# LB_BIT_i2_TOGGLESWITCH-v02_rev1.net
KiCad netlist of a schematic drawn in EAGLE
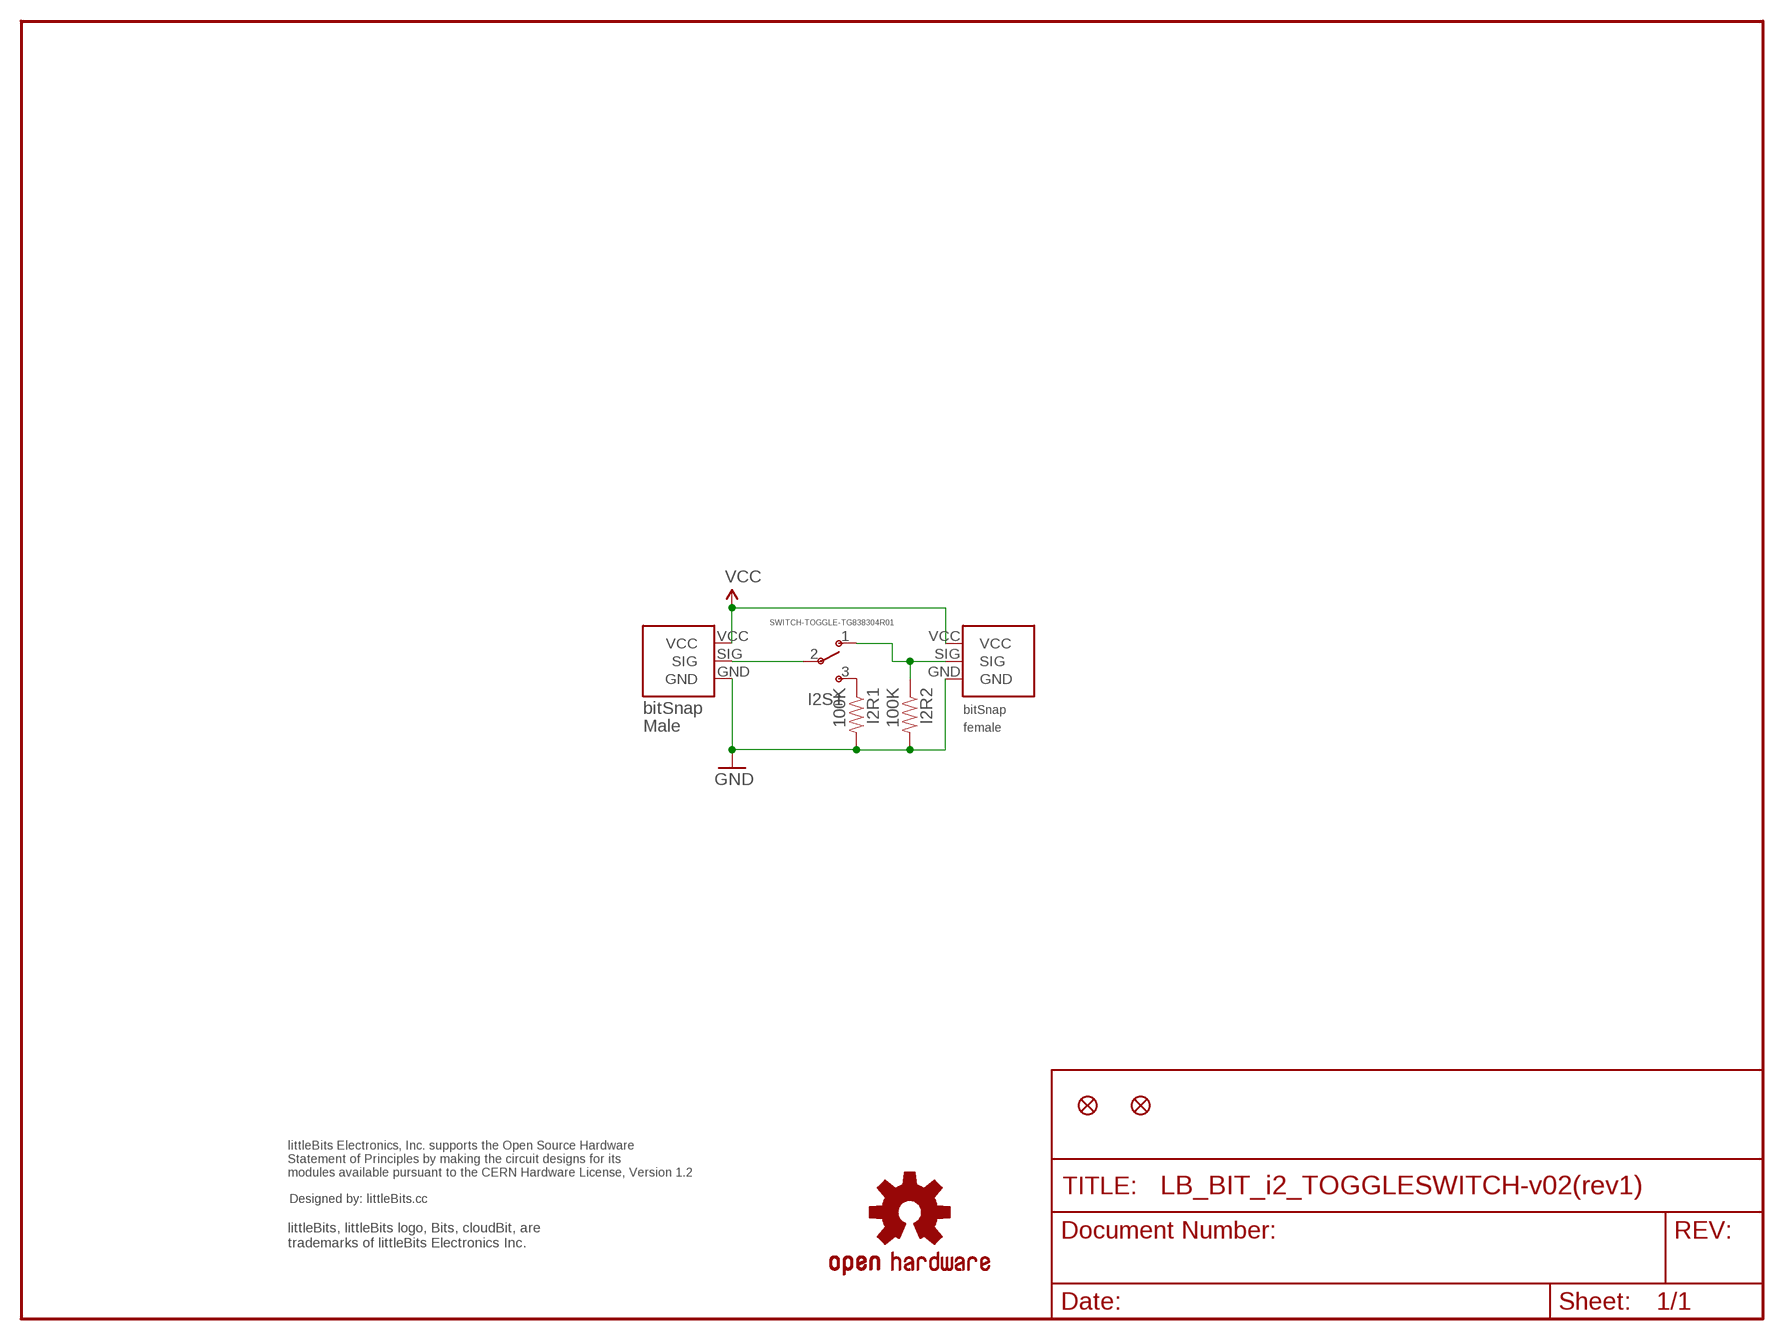
[diagram p0: schematic, sheet 1]

(export (version "E")
  (design (tool "Eeschema 10.0.6"))
  (components
    (comp (ref "I2BSF")
      (value "BITSNAP_FEMALE")
      (footprint "eagle-import:BITSNAP_FEMALE")
      (libsource (lib "eagle-import") (part "BITSNAP_FEMALE"))
    )
    (comp (ref "I2BSM")
      (value "BITSNAP_MALE")
      (footprint "eagle-import:BITSNAP_MALE")
      (libsource (lib "eagle-import") (part "BITSNAP_MALE"))
    )
    (comp (ref "I2R1")
      (value "100K")
      (footprint "eagle-import:0603-RES")
      (libsource (lib "eagle-import") (part "RESISTOR0603-RES"))
    )
    (comp (ref "I2R2")
      (value "100K")
      (footprint "eagle-import:0603-RES")
      (libsource (lib "eagle-import") (part "RESISTOR0603-RES"))
    )
    (comp (ref "I2S1")
      (value "SWITCH-TOGGLE-TG838304R01")
      (footprint "eagle-import:SWITCH-TOGGLE-TG838304R01")
      (libsource (lib "eagle-import") (part "SWITCH-TOGGLE-TG838304R01"))
    )
    (comp (ref "JP1")
      (value "FIDUCIAL1X2")
      (footprint "eagle-import:FIDUCIAL-1X2")
      (libsource (lib "eagle-import") (part "FIDUCIAL1X2"))
    )
    (comp (ref "JP2")
      (value "FIDUCIAL1X2")
      (footprint "eagle-import:FIDUCIAL-1X2")
      (libsource (lib "eagle-import") (part "FIDUCIAL1X2"))
    )
    (comp (ref "U$4")
      (value "OSHWCREDIT")
      (footprint "eagle-import:OSHWCREDIT")
      (libsource (lib "eagle-import") (part "OSHWCREDIT"))
    )
    (comp (ref "U$7")
      (value "OSHW-LOGOL")
      (footprint "eagle-import:OSHW-LOGO-L")
      (libsource (lib "eagle-import") (part "OSHW-LOGOL"))
    )
  )
  (nets
    (net (code "1") (name "GND") (class "Default")
      (node (ref "I2BSF") (pin "GND") (pinfunction "GND_GND") (pintype "bidirectional"))
      (node (ref "I2BSM") (pin "GND") (pinfunction "GND_GND") (pintype "bidirectional"))
      (node (ref "I2R1") (pin "2") (pinfunction "2_2") (pintype "passive"))
      (node (ref "I2R2") (pin "2") (pinfunction "2_2") (pintype "passive"))
    )
    (net (code "2") (name "Net-(I2S1-O)") (class "Default")
      (node (ref "I2BSF") (pin "SIG") (pinfunction "SIG_SIG") (pintype "bidirectional"))
      (node (ref "I2R2") (pin "1") (pinfunction "1_1") (pintype "passive"))
      (node (ref "I2S1") (pin "1") (pinfunction "O_1") (pintype "passive"))
    )
    (net (code "3") (name "Net-(I2S1-P)") (class "Default")
      (node (ref "I2BSM") (pin "SIG") (pinfunction "SIG_SIG") (pintype "bidirectional"))
      (node (ref "I2S1") (pin "2") (pinfunction "P_2") (pintype "passive"))
    )
    (net (code "4") (name "Net-(I2S1-S)") (class "Default")
      (node (ref "I2R1") (pin "1") (pinfunction "1_1") (pintype "passive"))
      (node (ref "I2S1") (pin "3") (pinfunction "S_3") (pintype "passive"))
    )
    (net (code "5") (name "VCC") (class "Default")
      (node (ref "I2BSF") (pin "VCC") (pinfunction "VCC_VCC") (pintype "bidirectional"))
      (node (ref "I2BSM") (pin "VCC") (pinfunction "VCC_VCC") (pintype "bidirectional"))
    )
  )
)
